# dss_v3.net
KiCad netlist of a schematic drawn in EAGLE
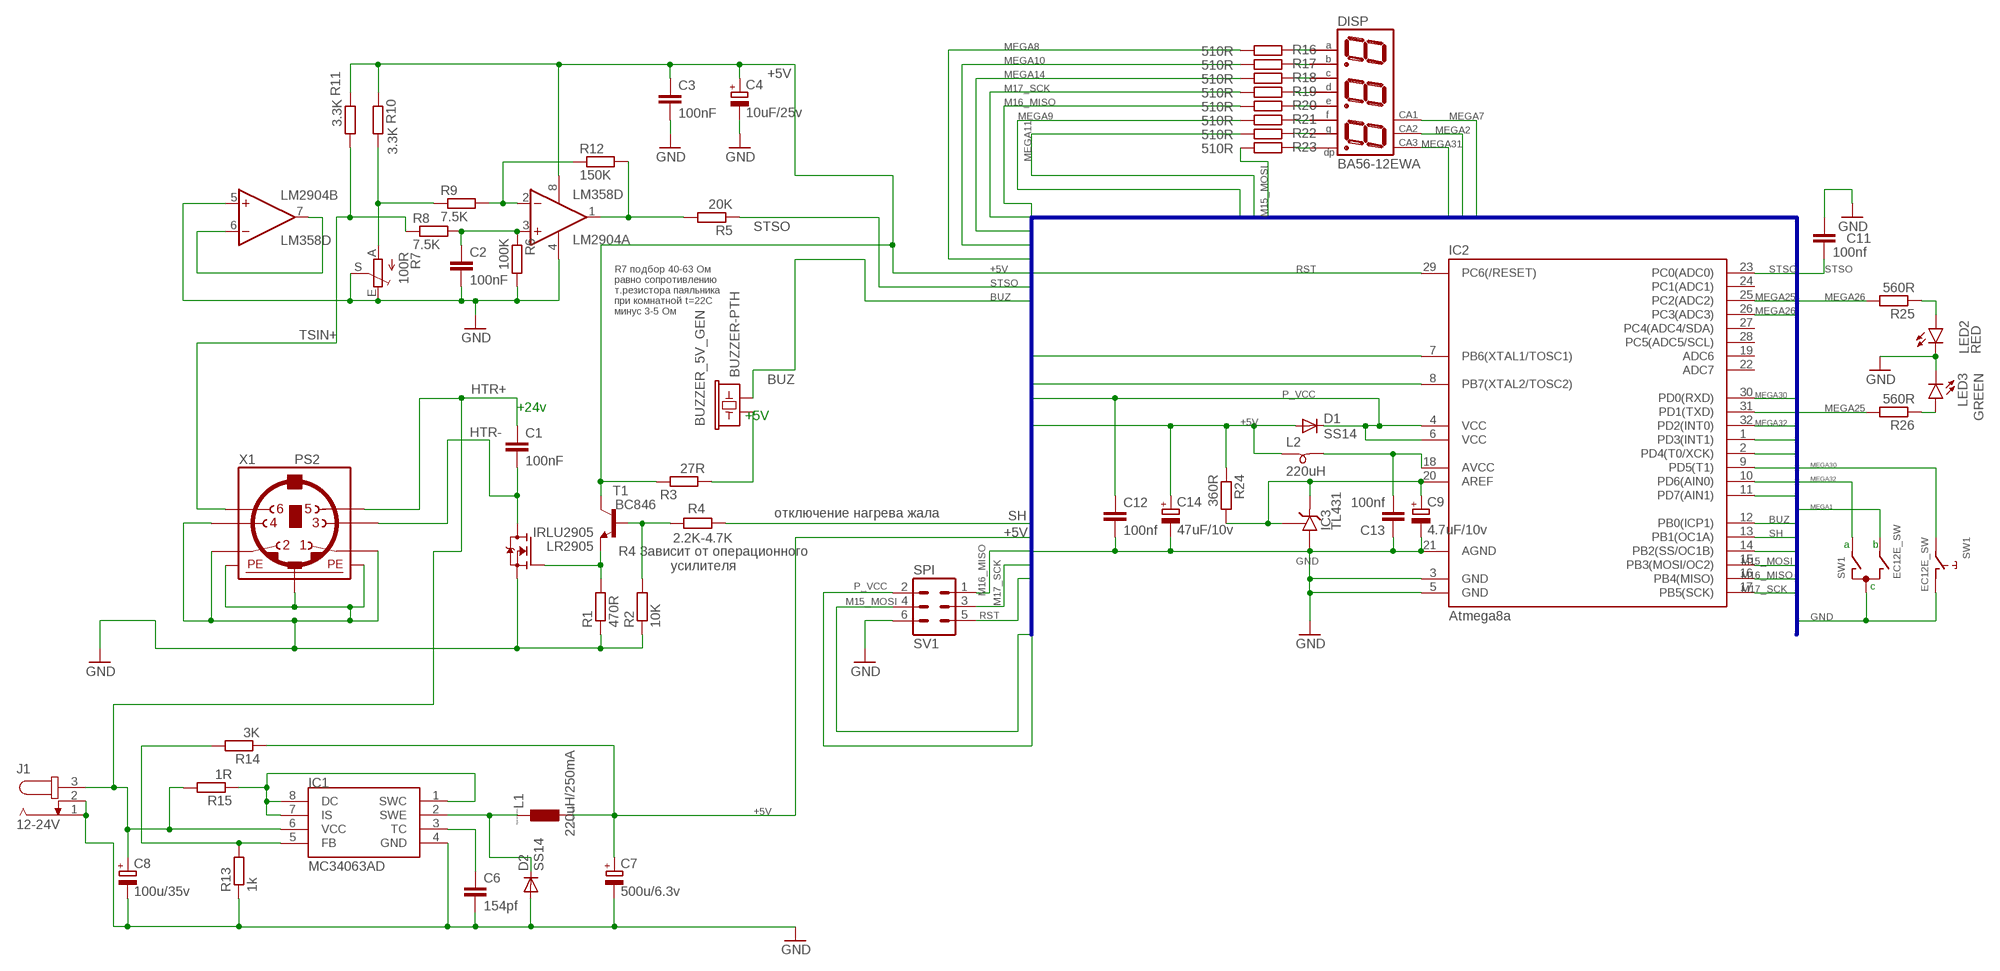
[diagram p0: schematic, sheet 1]

(export (version "E")
  (design (tool "Eeschema 10.0.6"))
  (components
    (comp (ref "BUZZER_5V_GEN")
      (value "BUZZER-PTH")
      (footprint "eagle-import:BUZZER-12MM")
      (libsource (lib "eagle-import") (part "BUZZER-PTH"))
    )
    (comp (ref "C1")
      (value "100nF")
      (footprint "eagle-import:C0805")
      (libsource (lib "eagle-import") (part "C-EUC0805"))
    )
    (comp (ref "C2")
      (value "100nF")
      (footprint "eagle-import:C0805")
      (libsource (lib "eagle-import") (part "C-EUC0805"))
    )
    (comp (ref "C3")
      (value "100nF")
      (footprint "eagle-import:C0805")
      (libsource (lib "eagle-import") (part "C-EUC0805"))
    )
    (comp (ref "C4")
      (value "10uF/25v")
      (footprint "eagle-import:CT3528")
      (libsource (lib "eagle-import") (part "rcl_334_CPOL-EUCT3528"))
    )
    (comp (ref "C6")
      (value "154pf")
      (footprint "eagle-import:C0805")
      (libsource (lib "eagle-import") (part "C-EUC0805"))
    )
    (comp (ref "C7")
      (value "500u/6.3v")
      (footprint "eagle-import:E3,5-8")
      (libsource (lib "eagle-import") (part "CPOL-EUE3.5-8"))
    )
    (comp (ref "C8")
      (value "100u/35v")
      (footprint "eagle-import:E3,5-8")
      (libsource (lib "eagle-import") (part "CPOL-EUE3.5-8"))
    )
    (comp (ref "C9")
      (value "4.7uF/10v")
      (footprint "eagle-import:CT3216")
      (libsource (lib "eagle-import") (part "rcl_334_CPOL-EUCT3216"))
    )
    (comp (ref "C11")
      (value "100nf")
      (footprint "eagle-import:C0805")
      (libsource (lib "eagle-import") (part "C-EUC0805"))
    )
    (comp (ref "C12")
      (value "100nf")
      (footprint "eagle-import:C0805")
      (libsource (lib "eagle-import") (part "C-EUC0805"))
    )
    (comp (ref "C13")
      (value "100nf")
      (footprint "eagle-import:C0805")
      (libsource (lib "eagle-import") (part "C-EUC0805"))
    )
    (comp (ref "C14")
      (value "47uF/10v")
      (footprint "eagle-import:CT3528")
      (libsource (lib "eagle-import") (part "rcl_334_CPOL-EUCT3528"))
    )
    (comp (ref "D1")
      (value "SS14")
      (footprint "eagle-import:DO214AC")
      (libsource (lib "eagle-import") (part "DIODE-DO214AC"))
    )
    (comp (ref "D2")
      (value "SS14")
      (footprint "eagle-import:DO214AC")
      (libsource (lib "eagle-import") (part "DIODE-DO214AC"))
    )
    (comp (ref "DISP")
      (value "BA56-12EWA")
      (footprint "eagle-import:BX56-12")
      (libsource (lib "eagle-import") (part "B?56-12WAAE"))
    )
    (comp (ref "IC1")
      (value "MC34063AD")
      (footprint "eagle-import:SOIC8")
      (libsource (lib "eagle-import") (part "MC34063AD"))
    )
    (comp (ref "IC2")
      (value "Atmega8a")
      (footprint "eagle-import:TQFP32-08")
      (libsource (lib "eagle-import") (part "ATMEGA8-AU"))
    )
    (comp (ref "IC3")
      (value "TL431")
      (footprint "eagle-import:SOT23")
      (libsource (lib "eagle-import") (part "TL431CLPSOT23"))
    )
    (comp (ref "IRLU2905")
      (value "LR2905")
      (footprint "eagle-import:TO252")
      (libsource (lib "eagle-import") (part "SPW47N60S5"))
    )
    (comp (ref "J1")
      (value "12-24V")
      (footprint "eagle-import:SPC4077")
      (libsource (lib "eagle-import") (part "JACK-PLUG0"))
    )
    (comp (ref "L1")
      (value "220uH/250mA")
      (footprint "eagle-import:L4532P")
      (libsource (lib "eagle-import") (part "LL4532P"))
    )
    (comp (ref "L2")
      (value "220uH")
      (footprint "eagle-import:SM-B5")
      (libsource (lib "eagle-import") (part "SM-B5"))
    )
    (comp (ref "LED2")
      (value "RED")
      (footprint "eagle-import:CHIP-LED0805")
      (libsource (lib "eagle-import") (part "LEDCHIP-LED0805"))
    )
    (comp (ref "LED3")
      (value "GREEN")
      (footprint "eagle-import:CHIP-LED0805")
      (libsource (lib "eagle-import") (part "LEDCHIP-LED0805"))
    )
    (comp (ref "LM2904")
      (value "LM358D")
      (footprint "eagle-import:SO08")
      (libsource (lib "eagle-import") (part "LM358D"))
    )
    (comp (ref "R1")
      (value "470R")
      (footprint "eagle-import:R0805")
      (libsource (lib "eagle-import") (part "rcl_334_R-EU_R0805"))
    )
    (comp (ref "R2")
      (value "10K")
      (footprint "eagle-import:R0805")
      (libsource (lib "eagle-import") (part "R-EU_R0805"))
    )
    (comp (ref "R3")
      (value "27R")
      (footprint "eagle-import:R0805")
      (libsource (lib "eagle-import") (part "R-EU_R0805"))
    )
    (comp (ref "R4")
      (value "2.2K-4.7K")
      (footprint "eagle-import:R0805")
      (libsource (lib "eagle-import") (part "R-EU_R0805"))
    )
    (comp (ref "R5")
      (value "20K")
      (footprint "eagle-import:R0805")
      (libsource (lib "eagle-import") (part "R-EU_R0805"))
    )
    (comp (ref "R6")
      (value "100K")
      (footprint "eagle-import:R0805")
      (libsource (lib "eagle-import") (part "R-EU_R0805"))
    )
    (comp (ref "R7")
      (value "100R")
      (footprint "eagle-import:B25P")
      (libsource (lib "eagle-import") (part "TRIM_EU-B25P"))
    )
    (comp (ref "R8")
      (value "7.5K")
      (footprint "eagle-import:R0805")
      (libsource (lib "eagle-import") (part "R-EU_R0805"))
    )
    (comp (ref "R9")
      (value "7.5K")
      (footprint "eagle-import:R0805")
      (libsource (lib "eagle-import") (part "R-EU_R0805"))
    )
    (comp (ref "R10")
      (value "3.3K")
      (footprint "eagle-import:R0805")
      (libsource (lib "eagle-import") (part "R-EU_R0805"))
    )
    (comp (ref "R11")
      (value "3.3K")
      (footprint "eagle-import:R0805")
      (libsource (lib "eagle-import") (part "R-EU_R0805"))
    )
    (comp (ref "R12")
      (value "150K")
      (footprint "eagle-import:R0805")
      (libsource (lib "eagle-import") (part "R-EU_R0805"))
    )
    (comp (ref "R13")
      (value "1k")
      (footprint "eagle-import:R0805")
      (libsource (lib "eagle-import") (part "R-EU_R0805"))
    )
    (comp (ref "R14")
      (value "3K")
      (footprint "eagle-import:R0805")
      (libsource (lib "eagle-import") (part "R-EU_R0805"))
    )
    (comp (ref "R15")
      (value "1R")
      (footprint "eagle-import:R0805")
      (libsource (lib "eagle-import") (part "R-EU_R0805"))
    )
    (comp (ref "R16")
      (value "510R")
      (footprint "eagle-import:R0805")
      (libsource (lib "eagle-import") (part "rcl_334_R-EU_R0805"))
    )
    (comp (ref "R17")
      (value "510R")
      (footprint "eagle-import:R0805")
      (libsource (lib "eagle-import") (part "rcl_334_R-EU_R0805"))
    )
    (comp (ref "R18")
      (value "510R")
      (footprint "eagle-import:R0805")
      (libsource (lib "eagle-import") (part "rcl_334_R-EU_R0805"))
    )
    (comp (ref "R19")
      (value "510R")
      (footprint "eagle-import:R0805")
      (libsource (lib "eagle-import") (part "rcl_334_R-EU_R0805"))
    )
    (comp (ref "R20")
      (value "510R")
      (footprint "eagle-import:R0805")
      (libsource (lib "eagle-import") (part "rcl_334_R-EU_R0805"))
    )
    (comp (ref "R21")
      (value "510R")
      (footprint "eagle-import:R0805")
      (libsource (lib "eagle-import") (part "rcl_334_R-EU_R0805"))
    )
    (comp (ref "R22")
      (value "510R")
      (footprint "eagle-import:R0805")
      (libsource (lib "eagle-import") (part "rcl_334_R-EU_R0805"))
    )
    (comp (ref "R23")
      (value "510R")
      (footprint "eagle-import:R0805")
      (libsource (lib "eagle-import") (part "rcl_334_R-EU_R0805"))
    )
    (comp (ref "R24")
      (value "360R")
      (footprint "eagle-import:R0805")
      (libsource (lib "eagle-import") (part "R-EU_R0805"))
    )
    (comp (ref "R25")
      (value "560R")
      (footprint "eagle-import:R0805")
      (libsource (lib "eagle-import") (part "rcl_334_R-EU_R0805"))
    )
    (comp (ref "R26")
      (value "560R")
      (footprint "eagle-import:R0805")
      (libsource (lib "eagle-import") (part "rcl_334_R-EU_R0805"))
    )
    (comp (ref "SV1")
      (value "SPI")
      (footprint "eagle-import:ML6")
      (libsource (lib "eagle-import") (part "ML6"))
    )
    (comp (ref "SW1")
      (value "EC12E_SW")
      (footprint "eagle-import:ALPS_EC12E_SW")
      (fields (field (name "MPN") "EC12E2424407"))
      (libsource (lib "eagle-import") (part "EC12E_SW"))
    )
    (comp (ref "T1")
      (value "BC846")
      (footprint "eagle-import:SOT23")
      (libsource (lib "eagle-import") (part "BC846"))
    )
    (comp (ref "X1")
      (value "PS2")
      (footprint "eagle-import:M_DIN6")
      (libsource (lib "eagle-import") (part "MINI_DIN_6"))
    )
  )
  (nets
    (net (code "1") (name "/+5V") (class "Default")
      (node (ref "C14") (pin "+") (pinfunction "+_+") (pintype "passive"))
      (node (ref "C3") (pin "1") (pinfunction "1_1") (pintype "passive"))
      (node (ref "C4") (pin "+") (pinfunction "+_+") (pintype "passive"))
      (node (ref "C7") (pin "+") (pinfunction "+_+") (pintype "passive"))
      (node (ref "D1") (pin "A") (pinfunction "A_A") (pintype "passive"))
      (node (ref "L1") (pin "2") (pinfunction "2_2") (pintype "passive"))
      (node (ref "L2") (pin "1") (pinfunction "1_1") (pintype "passive"))
      (node (ref "LM2904") (pin "8") (pinfunction "V+_8") (pintype "power_in"))
      (node (ref "R10") (pin "1") (pinfunction "1_1") (pintype "passive"))
      (node (ref "R11") (pin "1") (pinfunction "1_1") (pintype "passive"))
      (node (ref "R14") (pin "1") (pinfunction "1_1") (pintype "passive"))
      (node (ref "R24") (pin "1") (pinfunction "1_1") (pintype "passive"))
      (node (ref "R3") (pin "2") (pinfunction "2_2") (pintype "passive"))
      (node (ref "T1") (pin "3") (pinfunction "C_3") (pintype "passive"))
    )
    (net (code "2") (name "/BUZ") (class "Default")
      (node (ref "BUZZER_5V_GEN") (pin "-") (pinfunction "2_-") (pintype "passive"))
      (node (ref "IC2") (pin "12") (pinfunction "PB0(ICP1)_12") (pintype "bidirectional"))
    )
    (net (code "3") (name "/HTR+") (class "Default")
      (node (ref "C1") (pin "1") (pinfunction "1_1") (pintype "passive"))
      (node (ref "C8") (pin "+") (pinfunction "+_+") (pintype "passive"))
      (node (ref "IC1") (pin "6") (pinfunction "VCC_6") (pintype "passive"))
      (node (ref "J1") (pin "3") (pinfunction "3_3") (pintype "passive"))
      (node (ref "R15") (pin "2") (pinfunction "2_2") (pintype "passive"))
      (node (ref "X1") (pin "6") (pinfunction "6_6") (pintype "passive"))
    )
    (net (code "4") (name "/HTR-") (class "Default")
      (node (ref "C1") (pin "2") (pinfunction "2_2") (pintype "passive"))
      (node (ref "IRLU2905") (pin "4") (pinfunction "D_4") (pintype "passive"))
      (node (ref "X1") (pin "3") (pinfunction "3_3") (pintype "passive"))
    )
    (net (code "5") (name "/M15_MOSI") (class "Default")
      (node (ref "IC2") (pin "15") (pinfunction "PB3(MOSI/OC2)_15") (pintype "bidirectional"))
      (node (ref "R23") (pin "2") (pinfunction "2_2") (pintype "passive"))
      (node (ref "SV1") (pin "4") (pinfunction "4_4") (pintype "passive"))
    )
    (net (code "6") (name "/M16_MISO") (class "Default")
      (node (ref "IC2") (pin "16") (pinfunction "PB4(MISO)_16") (pintype "bidirectional"))
      (node (ref "R20") (pin "2") (pinfunction "2_2") (pintype "passive"))
      (node (ref "SV1") (pin "1") (pinfunction "1_1") (pintype "passive"))
    )
    (net (code "7") (name "/M17_SCK") (class "Default")
      (node (ref "IC2") (pin "17") (pinfunction "PB5(SCK)_17") (pintype "bidirectional"))
      (node (ref "R19") (pin "2") (pinfunction "2_2") (pintype "passive"))
      (node (ref "SV1") (pin "3") (pinfunction "3_3") (pintype "passive"))
    )
    (net (code "8") (name "/MEGA1") (class "Default")
      (node (ref "IC2") (pin "1") (pinfunction "PD3(INT1)_1") (pintype "bidirectional"))
      (node (ref "SW1") (pin "B") (pinfunction "B_B") (pintype "passive"))
    )
    (net (code "9") (name "/MEGA2") (class "Default")
      (node (ref "DISP") (pin "9") (pinfunction "CA_9") (pintype "passive"))
      (node (ref "IC2") (pin "2") (pinfunction "PD4(T0/XCK)_2") (pintype "bidirectional"))
    )
    (net (code "10") (name "/MEGA7") (class "Default")
      (node (ref "DISP") (pin "12") (pinfunction "CA_12") (pintype "passive"))
      (node (ref "IC2") (pin "7") (pinfunction "PB6(XTAL1/TOSC1)_7") (pintype "bidirectional"))
    )
    (net (code "11") (name "/MEGA8") (class "Default")
      (node (ref "IC2") (pin "8") (pinfunction "PB7(XTAL2/TOSC2)_8") (pintype "bidirectional"))
      (node (ref "R16") (pin "2") (pinfunction "2_2") (pintype "passive"))
    )
    (net (code "12") (name "/MEGA9") (class "Default")
      (node (ref "IC2") (pin "9") (pinfunction "PD5(T1)_9") (pintype "bidirectional"))
      (node (ref "R21") (pin "2") (pinfunction "2_2") (pintype "passive"))
    )
    (net (code "13") (name "/MEGA10") (class "Default")
      (node (ref "IC2") (pin "10") (pinfunction "PD6(AIN0)_10") (pintype "bidirectional"))
      (node (ref "R17") (pin "2") (pinfunction "2_2") (pintype "passive"))
    )
    (net (code "14") (name "/MEGA11") (class "Default")
      (node (ref "IC2") (pin "11") (pinfunction "PD7(AIN1)_11") (pintype "bidirectional"))
      (node (ref "R22") (pin "2") (pinfunction "2_2") (pintype "passive"))
    )
    (net (code "15") (name "/MEGA14") (class "Default")
      (node (ref "IC2") (pin "14") (pinfunction "PB2(SS/OC1B)_14") (pintype "bidirectional"))
      (node (ref "R18") (pin "2") (pinfunction "2_2") (pintype "passive"))
    )
    (net (code "16") (name "/MEGA25") (class "Default")
      (node (ref "IC2") (pin "25") (pinfunction "PC2(ADC2)_25") (pintype "bidirectional"))
      (node (ref "R26") (pin "2") (pinfunction "2_2") (pintype "passive"))
    )
    (net (code "17") (name "/MEGA26") (class "Default")
      (node (ref "IC2") (pin "26") (pinfunction "PC3(ADC3)_26") (pintype "bidirectional"))
      (node (ref "R25") (pin "2") (pinfunction "2_2") (pintype "passive"))
    )
    (net (code "18") (name "/MEGA30") (class "Default")
      (node (ref "IC2") (pin "30") (pinfunction "PD0(RXD)_30") (pintype "bidirectional"))
      (node (ref "SW1") (pin "E") (pinfunction "2_E") (pintype "passive"))
    )
    (net (code "19") (name "/MEGA31") (class "Default")
      (node (ref "DISP") (pin "8") (pinfunction "CA_8") (pintype "passive"))
      (node (ref "IC2") (pin "31") (pinfunction "PD1(TXD)_31") (pintype "bidirectional"))
    )
    (net (code "20") (name "/MEGA32") (class "Default")
      (node (ref "IC2") (pin "32") (pinfunction "PD2(INT0)_32") (pintype "bidirectional"))
      (node (ref "SW1") (pin "A") (pinfunction "A_A") (pintype "passive"))
    )
    (net (code "21") (name "/P_VCC") (class "Default")
      (node (ref "C12") (pin "1") (pinfunction "1_1") (pintype "passive"))
      (node (ref "D1") (pin "C") (pinfunction "C_C") (pintype "passive"))
      (node (ref "IC2") (pin "4") (pinfunction "VCC_4") (pintype "power_in"))
      (node (ref "IC2") (pin "6") (pinfunction "VCC_6") (pintype "power_in"))
      (node (ref "SV1") (pin "2") (pinfunction "2_2") (pintype "passive"))
    )
    (net (code "22") (name "/RST") (class "Default")
      (node (ref "IC2") (pin "29") (pinfunction "PC6(/RESET)_29") (pintype "bidirectional"))
      (node (ref "SV1") (pin "5") (pinfunction "5_5") (pintype "passive"))
    )
    (net (code "23") (name "/SH") (class "Default")
      (node (ref "IC2") (pin "13") (pinfunction "PB1(OC1A)_13") (pintype "bidirectional"))
      (node (ref "R4") (pin "1") (pinfunction "1_1") (pintype "passive"))
    )
    (net (code "24") (name "/STSO") (class "Default")
      (node (ref "C11") (pin "2") (pinfunction "2_2") (pintype "passive"))
      (node (ref "IC2") (pin "23") (pinfunction "PC0(ADC0)_23") (pintype "bidirectional"))
      (node (ref "R5") (pin "1") (pinfunction "1_1") (pintype "passive"))
    )
    (net (code "25") (name "/TSIN+") (class "Default")
      (node (ref "R11") (pin "2") (pinfunction "2_2") (pintype "passive"))
      (node (ref "R8") (pin "1") (pinfunction "1_1") (pintype "passive"))
      (node (ref "X1") (pin "8") (pinfunction "8_8") (pintype "passive"))
    )
    (net (code "26") (name "GND") (class "Default")
      (node (ref "C11") (pin "1") (pinfunction "1_1") (pintype "passive"))
      (node (ref "C12") (pin "2") (pinfunction "2_2") (pintype "passive"))
      (node (ref "C13") (pin "1") (pinfunction "1_1") (pintype "passive"))
      (node (ref "C14") (pin "-") (pinfunction "-_-") (pintype "passive"))
      (node (ref "C2") (pin "2") (pinfunction "2_2") (pintype "passive"))
      (node (ref "C3") (pin "2") (pinfunction "2_2") (pintype "passive"))
      (node (ref "C4") (pin "-") (pinfunction "-_-") (pintype "passive"))
      (node (ref "C6") (pin "2") (pinfunction "2_2") (pintype "passive"))
      (node (ref "C7") (pin "-") (pinfunction "-_-") (pintype "passive"))
      (node (ref "C8") (pin "-") (pinfunction "-_-") (pintype "passive"))
      (node (ref "C9") (pin "-") (pinfunction "-_-") (pintype "passive"))
      (node (ref "D2") (pin "A") (pinfunction "A_A") (pintype "passive"))
      (node (ref "IC1") (pin "4") (pinfunction "GND_4") (pintype "passive"))
      (node (ref "IC2") (pin "21") (pinfunction "AGND_21") (pintype "power_in"))
      (node (ref "IC2") (pin "3") (pinfunction "GND_3") (pintype "power_in"))
      (node (ref "IC2") (pin "5") (pinfunction "GND_5") (pintype "power_in"))
      (node (ref "IC3") (pin "3") (pinfunction "A_3") (pintype "passive"))
      (node (ref "IRLU2905") (pin "3") (pinfunction "S_3") (pintype "passive"))
      (node (ref "J1") (pin "1") (pinfunction "1_1") (pintype "passive"))
      (node (ref "J1") (pin "2") (pinfunction "2_2") (pintype "passive"))
      (node (ref "LED2") (pin "C") (pinfunction "C_C") (pintype "passive"))
      (node (ref "LED3") (pin "C") (pinfunction "C_C") (pintype "passive"))
      (node (ref "LM2904") (pin "4") (pinfunction "V-_4") (pintype "power_in"))
      (node (ref "LM2904") (pin "5") (pinfunction "+IN_5") (pintype "input"))
      (node (ref "R1") (pin "1") (pinfunction "1_1") (pintype "passive"))
      (node (ref "R13") (pin "1") (pinfunction "1_1") (pintype "passive"))
      (node (ref "R2") (pin "1") (pinfunction "1_1") (pintype "passive"))
      (node (ref "R6") (pin "2") (pinfunction "2_2") (pintype "passive"))
      (node (ref "R7") (pin "E") (pinfunction "E_E") (pintype "passive"))
      (node (ref "R7") (pin "S") (pinfunction "S_S") (pintype "passive"))
      (node (ref "SV1") (pin "6") (pinfunction "6_6") (pintype "passive"))
      (node (ref "SW1") (pin "C") (pinfunction "C_C") (pintype "passive"))
      (node (ref "SW1") (pin "D") (pinfunction "1_D") (pintype "passive"))
      (node (ref "X1") (pin "1") (pinfunction "1_1") (pintype "passive"))
      (node (ref "X1") (pin "2") (pinfunction "2_2") (pintype "passive"))
      (node (ref "X1") (pin "5") (pinfunction "5_5") (pintype "passive"))
      (node (ref "X1") (pin "SH1") (pinfunction "PE1_SH1") (pintype "power_in"))
      (node (ref "X1") (pin "SH2") (pinfunction "PE2_SH2") (pintype "power_in"))
      (node (ref "X1") (pin "SH3") (pinfunction "PE3_SH3") (pintype "power_in"))
    )
    (net (code "27") (name "Net-(BUZZER_5V_GEN-1)") (class "Default")
      (node (ref "BUZZER_5V_GEN") (pin "+") (pinfunction "1_+") (pintype "passive"))
      (node (ref "R3") (pin "1") (pinfunction "1_1") (pintype "passive"))
    )
    (net (code "28") (name "Net-(DISP-A)") (class "Default")
      (node (ref "DISP") (pin "11") (pinfunction "A_11") (pintype "passive"))
      (node (ref "R16") (pin "1") (pinfunction "1_1") (pintype "passive"))
    )
    (net (code "29") (name "Net-(DISP-B)") (class "Default")
      (node (ref "DISP") (pin "7") (pinfunction "B_7") (pintype "passive"))
      (node (ref "R17") (pin "1") (pinfunction "1_1") (pintype "passive"))
    )
    (net (code "30") (name "Net-(DISP-C)") (class "Default")
      (node (ref "DISP") (pin "4") (pinfunction "C_4") (pintype "passive"))
      (node (ref "R18") (pin "1") (pinfunction "1_1") (pintype "passive"))
    )
    (net (code "31") (name "Net-(DISP-D)") (class "Default")
      (node (ref "DISP") (pin "2") (pinfunction "D_2") (pintype "passive"))
      (node (ref "R19") (pin "1") (pinfunction "1_1") (pintype "passive"))
    )
    (net (code "32") (name "Net-(DISP-DP)") (class "Default")
      (node (ref "DISP") (pin "3") (pinfunction "DP_3") (pintype "passive"))
      (node (ref "R23") (pin "1") (pinfunction "1_1") (pintype "passive"))
    )
    (net (code "33") (name "Net-(DISP-E)") (class "Default")
      (node (ref "DISP") (pin "1") (pinfunction "E_1") (pintype "passive"))
      (node (ref "R20") (pin "1") (pinfunction "1_1") (pintype "passive"))
    )
    (net (code "34") (name "Net-(DISP-F)") (class "Default")
      (node (ref "DISP") (pin "10") (pinfunction "F_10") (pintype "passive"))
      (node (ref "R21") (pin "1") (pinfunction "1_1") (pintype "passive"))
    )
    (net (code "35") (name "Net-(DISP-G)") (class "Default")
      (node (ref "DISP") (pin "5") (pinfunction "G_5") (pintype "passive"))
      (node (ref "R22") (pin "1") (pinfunction "1_1") (pintype "passive"))
    )
    (net (code "36") (name "Net-(IC1-DC)") (class "Default")
      (node (ref "IC1") (pin "1") (pinfunction "SWC_1") (pintype "passive"))
      (node (ref "IC1") (pin "7") (pinfunction "IS_7") (pintype "passive"))
      (node (ref "IC1") (pin "8") (pinfunction "DC_8") (pintype "passive"))
      (node (ref "R15") (pin "1") (pinfunction "1_1") (pintype "passive"))
    )
    (net (code "37") (name "Net-(IC1-FB)") (class "Default")
      (node (ref "IC1") (pin "5") (pinfunction "FB_5") (pintype "passive"))
      (node (ref "R13") (pin "2") (pinfunction "2_2") (pintype "passive"))
      (node (ref "R14") (pin "2") (pinfunction "2_2") (pintype "passive"))
    )
    (net (code "38") (name "Net-(IC1-SWE)") (class "Default")
      (node (ref "D2") (pin "C") (pinfunction "C_C") (pintype "passive"))
      (node (ref "IC1") (pin "2") (pinfunction "SWE_2") (pintype "passive"))
      (node (ref "L1") (pin "1") (pinfunction "1_1") (pintype "passive"))
    )
    (net (code "39") (name "Net-(IC1-TC)") (class "Default")
      (node (ref "C6") (pin "1") (pinfunction "1_1") (pintype "passive"))
      (node (ref "IC1") (pin "3") (pinfunction "TC_3") (pintype "passive"))
    )
    (net (code "40") (name "Net-(IC2-AREF)") (class "Default")
      (node (ref "C9") (pin "+") (pinfunction "+_+") (pintype "passive"))
      (node (ref "IC2") (pin "20") (pinfunction "AREF_20") (pintype "passive"))
      (node (ref "IC3") (pin "1") (pinfunction "C_1") (pintype "passive"))
      (node (ref "IC3") (pin "2") (pinfunction "R_2") (pintype "passive"))
      (node (ref "R24") (pin "2") (pinfunction "2_2") (pintype "passive"))
    )
    (net (code "41") (name "Net-(IC2-AVCC)") (class "Default")
      (node (ref "C13") (pin "2") (pinfunction "2_2") (pintype "passive"))
      (node (ref "IC2") (pin "18") (pinfunction "AVCC_18") (pintype "passive"))
      (node (ref "L2") (pin "2") (pinfunction "2_2") (pintype "passive"))
    )
    (net (code "42") (name "Net-(IRLU2905-G)") (class "Default")
      (node (ref "IRLU2905") (pin "1") (pinfunction "G_1") (pintype "passive"))
      (node (ref "R1") (pin "2") (pinfunction "2_2") (pintype "passive"))
      (node (ref "T1") (pin "2") (pinfunction "E_2") (pintype "passive"))
    )
    (net (code "43") (name "Net-(LED2-PadA)") (class "Default")
      (node (ref "LED2") (pin "A") (pinfunction "A_A") (pintype "passive"))
      (node (ref "R25") (pin "1") (pinfunction "1_1") (pintype "passive"))
    )
    (net (code "44") (name "Net-(LED3-PadA)") (class "Default")
      (node (ref "LED3") (pin "A") (pinfunction "A_A") (pintype "passive"))
      (node (ref "R26") (pin "1") (pinfunction "1_1") (pintype "passive"))
    )
    (net (code "45") (name "Net-(LM2904A-+IN)") (class "Default")
      (node (ref "C2") (pin "1") (pinfunction "1_1") (pintype "passive"))
      (node (ref "LM2904") (pin "3") (pinfunction "+IN_3") (pintype "input"))
      (node (ref "R6") (pin "1") (pinfunction "1_1") (pintype "passive"))
      (node (ref "R8") (pin "2") (pinfunction "2_2") (pintype "passive"))
    )
    (net (code "46") (name "Net-(LM2904A--IN)") (class "Default")
      (node (ref "LM2904") (pin "2") (pinfunction "-IN_2") (pintype "input"))
      (node (ref "R12") (pin "1") (pinfunction "1_1") (pintype "passive"))
      (node (ref "R9") (pin "2") (pinfunction "2_2") (pintype "passive"))
    )
    (net (code "47") (name "Net-(LM2904A-OUT)") (class "Default")
      (node (ref "LM2904") (pin "1") (pinfunction "OUT_1") (pintype "output"))
      (node (ref "R12") (pin "2") (pinfunction "2_2") (pintype "passive"))
      (node (ref "R5") (pin "2") (pinfunction "2_2") (pintype "passive"))
    )
    (net (code "48") (name "Net-(LM2904B--IN)") (class "Default")
      (node (ref "LM2904") (pin "6") (pinfunction "-IN_6") (pintype "input"))
      (node (ref "LM2904") (pin "7") (pinfunction "OUT_7") (pintype "output"))
    )
    (net (code "49") (name "Net-(R10-Pad2)") (class "Default")
      (node (ref "R10") (pin "2") (pinfunction "2_2") (pintype "passive"))
      (node (ref "R7") (pin "A") (pinfunction "A_A") (pintype "passive"))
      (node (ref "R9") (pin "1") (pinfunction "1_1") (pintype "passive"))
    )
    (net (code "50") (name "Net-(T1-B)") (class "Default")
      (node (ref "R2") (pin "2") (pinfunction "2_2") (pintype "passive"))
      (node (ref "R4") (pin "2") (pinfunction "2_2") (pintype "passive"))
      (node (ref "T1") (pin "1") (pinfunction "B_1") (pintype "passive"))
    )
    (net (code "51") (name "unconnected-(IC2-ADC6-Pad19)") (class "Default")
      (node (ref "IC2") (pin "19") (pinfunction "ADC6_19") (pintype "passive"))
    )
    (net (code "52") (name "unconnected-(IC2-ADC7-Pad22)") (class "Default")
      (node (ref "IC2") (pin "22") (pinfunction "ADC7_22") (pintype "passive"))
    )
    (net (code "53") (name "unconnected-(IC2-PC1(ADC1)-Pad24)") (class "Default")
      (node (ref "IC2") (pin "24") (pinfunction "PC1(ADC1)_24") (pintype "bidirectional"))
    )
    (net (code "54") (name "unconnected-(IC2-PC4(ADC4{slash}SDA)-Pad27)") (class "Default")
      (node (ref "IC2") (pin "27") (pinfunction "PC4(ADC4/SDA)_27") (pintype "bidirectional"))
    )
    (net (code "55") (name "unconnected-(IC2-PC5(ADC5{slash}SCL)-Pad28)") (class "Default")
      (node (ref "IC2") (pin "28") (pinfunction "PC5(ADC5/SCL)_28") (pintype "bidirectional"))
    )
  )
)
